# DWDM_-.net
KiCad netlist of a schematic drawn in Altium Designer
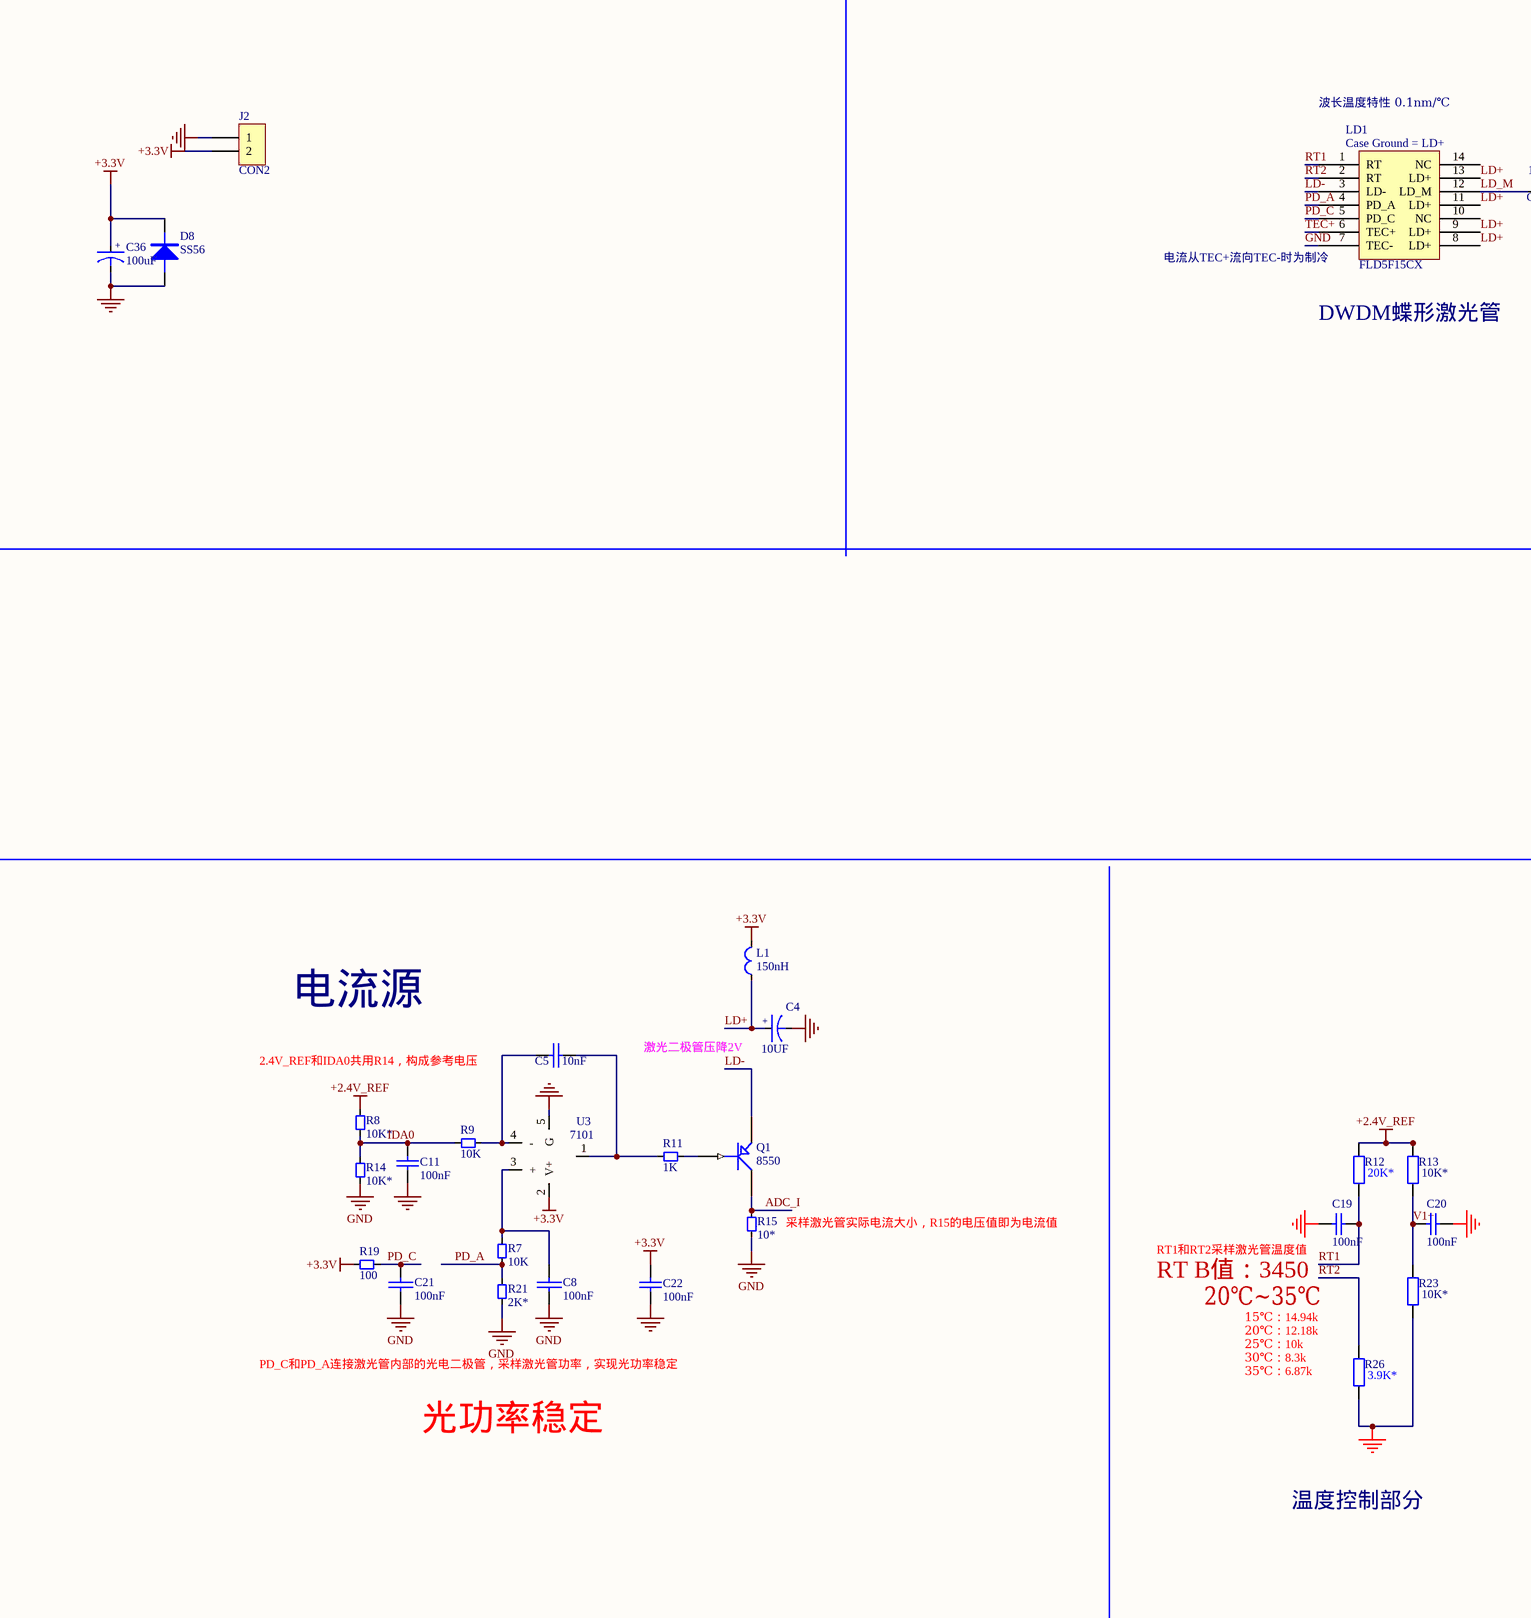
[diagram p0: DWDM蝶形激光管驱动器-线性.SchDoc, left]
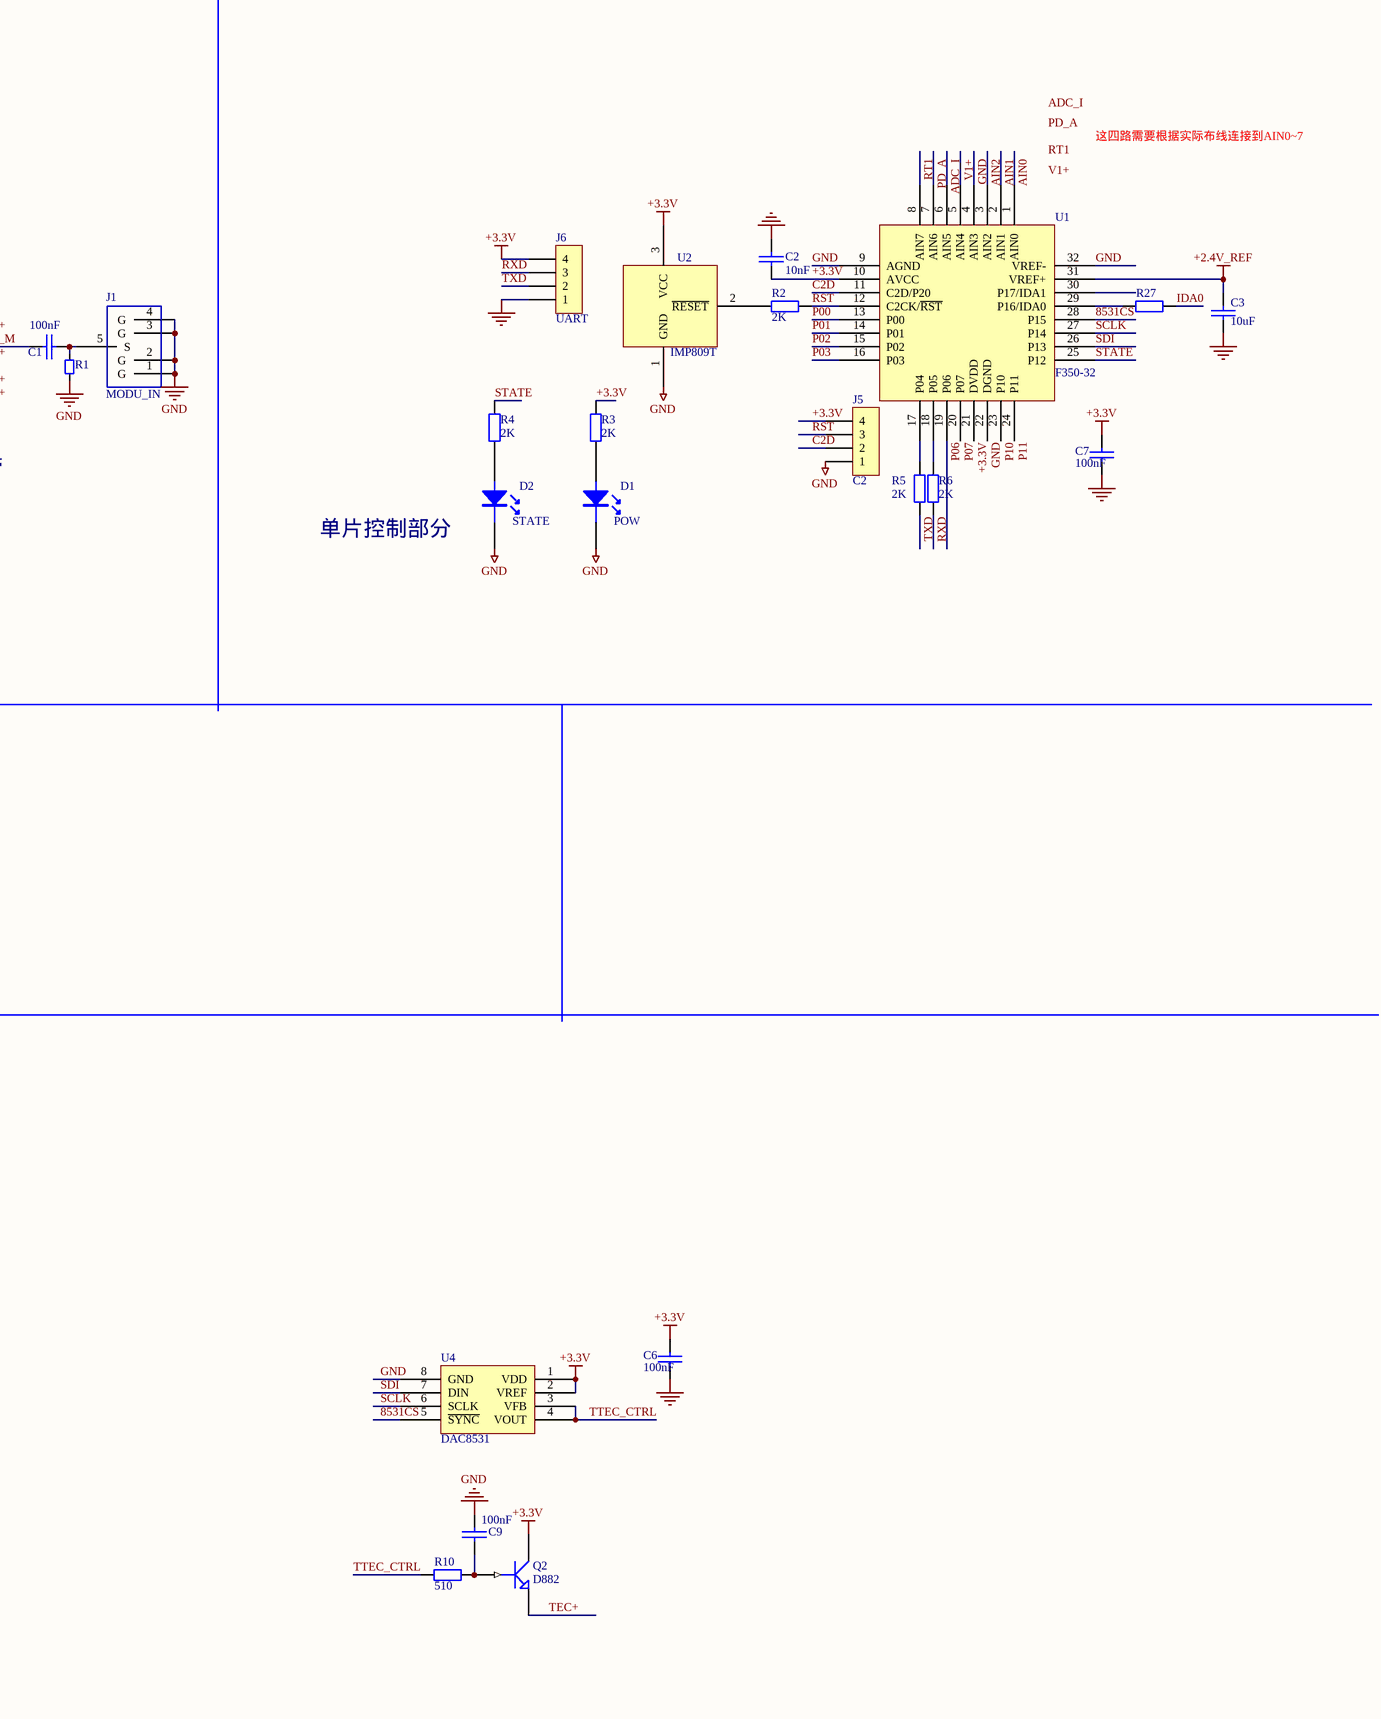
[diagram p1: DWDM蝶形激光管驱动器-线性.SchDoc, right]

(export (version "E")
  (design (tool "Eeschema 10.0.6"))
  (components
    (comp (ref "C1")
      (value "100nF")
      (footprint "0805")
      (description "Capacitor")
      (libsource (lib "*") (part "CAP"))
    )
    (comp (ref "C2")
      (value "10nF")
      (footprint "0805")
      (description "Capacitor")
      (libsource (lib "*") (part "CAP"))
    )
    (comp (ref "C3")
      (value "10uF")
      (footprint "0805")
      (description "Capacitor")
      (libsource (lib "*") (part "CAP"))
    )
    (comp (ref "C4") (value "10UF") (footprint "1206-C") (libsource (lib "高精时频SCHLIB") (part "CAP-POL-TA")))
    (comp (ref "C5")
      (value "10nF")
      (footprint "0805")
      (description "Capacitor")
      (libsource (lib "*") (part "CAP"))
    )
    (comp (ref "C6")
      (value "100nF")
      (footprint "0805")
      (description "Capacitor")
      (libsource (lib "*") (part "CAP"))
    )
    (comp (ref "C7")
      (value "100nF")
      (footprint "0805")
      (description "Capacitor")
      (libsource (lib "*") (part "CAP"))
    )
    (comp (ref "C8")
      (value "100nF")
      (footprint "0805")
      (description "Capacitor")
      (libsource (lib "*") (part "CAP"))
    )
    (comp (ref "C9")
      (value "100nF")
      (footprint "0805")
      (description "Capacitor")
      (libsource (lib "*") (part "CAP"))
    )
    (comp (ref "C11")
      (value "100nF")
      (footprint "0805")
      (description "Capacitor")
      (libsource (lib "*") (part "Cap"))
    )
    (comp (ref "C19")
      (value "100nF")
      (footprint "0805")
      (description "Capacitor")
      (libsource (lib "*") (part "Cap"))
    )
    (comp (ref "C20")
      (value "100nF")
      (footprint "0805")
      (description "Capacitor")
      (libsource (lib "*") (part "Cap"))
    )
    (comp (ref "C21")
      (value "100nF")
      (footprint "0805")
      (description "Capacitor")
      (libsource (lib "*") (part "CAP"))
    )
    (comp (ref "C22")
      (value "100nF")
      (footprint "0805")
      (description "Capacitor")
      (libsource (lib "*") (part "Cap"))
    )
    (comp (ref "C36") (value "100uF") (footprint "C6032") (libsource (lib "高精时频SCHLIB") (part "CAP-POL-TA")))
    (comp (ref "D1") (value "POW") (footprint "LED.3") (libsource (lib "*") (part "LED")))
    (comp (ref "D2") (value "STATE") (footprint "LED.3") (libsource (lib "*") (part "LED")))
    (comp (ref "D8") (value "SS56") (footprint "1808D-") (libsource (lib "高精时频SCHLIB") (part "DIODE")))
    (comp (ref "J1") (value "MODU_IN") (footprint "SMA") (libsource (lib "高精时频SCHLIB") (part "SMA")))
    (comp (ref "J2")
      (value "CON2")
      (footprint "JK2-394-F")
      (description "Connector")
      (libsource (lib "高精时频SCHLIB") (part "CON2"))
    )
    (comp (ref "J5")
      (value "C2")
      (footprint "SIP-4-Z")
      (description "Connector")
      (libsource (lib "*") (part "CON4"))
    )
    (comp (ref "J6")
      (value "UART")
      (footprint "SIP-4-Z")
      (description "Connector")
      (libsource (lib "*") (part "CON4"))
    )
    (comp (ref "L1") (value "150nH") (footprint "0805") (libsource (lib "高精时频SCHLIB") (part "INDUCTOR")))
    (comp (ref "LD1")
      (value "FLD5F15CX")
      (footprint "CM96/LC97-N")
      (libsource (lib "CFX") (part "FLD5F15CX"))
    )
    (comp (ref "Q1") (value "8550") (footprint "SOT-23") (libsource (lib "高精时频SCHLIB") (part "PNP-SOT23")))
    (comp (ref "Q2")
      (value "D882")
      (footprint "TO-252-D882")
      (libsource (lib "高精时频SCHLIB") (part "NPN-TO252"))
    )
    (comp (ref "R1") (value "~") (footprint "0805") (libsource (lib "高精时频SCHLIB") (part "RES")))
    (comp (ref "R2") (value "2K") (footprint "0805") (libsource (lib "") (part "RES2_1")))
    (comp (ref "R3") (value "2K") (footprint "0805") (libsource (lib "*") (part "RES2")))
    (comp (ref "R4") (value "2K") (footprint "0805") (libsource (lib "*") (part "RES2")))
    (comp (ref "R5") (value "2K") (footprint "0805") (libsource (lib "*") (part "RES2")))
    (comp (ref "R6") (value "2K") (footprint "0805") (libsource (lib "*") (part "RES2")))
    (comp (ref "R7") (value "10K") (footprint "0805") (libsource (lib "高精时频SCHLIB") (part "RES")))
    (comp (ref "R8") (value "10K*") (footprint "0805") (libsource (lib "高精时频SCHLIB") (part "RES")))
    (comp (ref "R9") (value "10K") (footprint "0805") (libsource (lib "高精时频SCHLIB") (part "RES")))
    (comp (ref "R10") (value "510") (footprint "0805") (libsource (lib "") (part "RES2_1")))
    (comp (ref "R11") (value "1K") (footprint "0805") (libsource (lib "高精时频SCHLIB") (part "RES")))
    (comp (ref "R12")
      (value "20K*")
      (footprint "0805")
      (description "Resistor")
      (libsource (lib "*") (part "Res2"))
    )
    (comp (ref "R13")
      (value "10K*")
      (footprint "0805")
      (description "Resistor")
      (libsource (lib "*") (part "Res2"))
    )
    (comp (ref "R14") (value "10K*") (footprint "0805") (libsource (lib "高精时频SCHLIB") (part "RES")))
    (comp (ref "R15") (value "10*") (footprint "0805") (libsource (lib "高精时频SCHLIB") (part "RES")))
    (comp (ref "R19") (value "100") (footprint "0805") (libsource (lib "高精时频SCHLIB") (part "RES")))
    (comp (ref "R21") (value "2K*") (footprint "0805") (libsource (lib "高精时频SCHLIB") (part "RES")))
    (comp (ref "R23")
      (value "10K*")
      (footprint "0805")
      (description "Resistor")
      (libsource (lib "*") (part "Res2"))
    )
    (comp (ref "R26")
      (value "3.9K*")
      (footprint "0805")
      (description "Resistor")
      (libsource (lib "*") (part "Res2"))
    )
    (comp (ref "R27") (value "~") (footprint "0805") (libsource (lib "") (part "RES2_1")))
    (comp (ref "U1") (value "F350-32") (footprint "LQFP32") (libsource (lib "*") (part "C8051F350-32")))
    (comp (ref "U2") (value "IMP809T") (footprint "SOT-23-P") (libsource (lib "*") (part "IMP809")))
    (comp (ref "U3") (value "7101") (footprint "PDSO-G5-DBV") (libsource (lib "*") (part "LMC7101")))
    (comp (ref "U4") (value "DAC8531") (footprint "PDSO-G8-DGK") (libsource (lib "*") (part "DAC8531")))
  )
  (nets
    (net (code "1") (name "+2.4V_REF") (class "Default")
      (node (ref "C3") (pin "1") (pinfunction "1_1") (pintype "passive"))
      (node (ref "R12") (pin "2") (pinfunction "2_2") (pintype "passive"))
      (node (ref "R13") (pin "2") (pinfunction "2_2") (pintype "passive"))
      (node (ref "R8") (pin "2") (pinfunction "2_2") (pintype "passive"))
      (node (ref "U1") (pin "31") (pinfunction "VREF+_31") (pintype "passive"))
    )
    (net (code "2") (name "+3.3V") (class "Default")
      (node (ref "C2") (pin "1") (pinfunction "1_1") (pintype "passive"))
      (node (ref "C22") (pin "2") (pinfunction "2_2") (pintype "passive"))
      (node (ref "C36") (pin "1") (pinfunction "1_1") (pintype "passive"))
      (node (ref "C6") (pin "1") (pinfunction "1_1") (pintype "passive"))
      (node (ref "C7") (pin "1") (pinfunction "1_1") (pintype "passive"))
      (node (ref "D8") (pin "2") (pinfunction "Cathode_2") (pintype "passive"))
      (node (ref "J2") (pin "2") (pinfunction "2_2") (pintype "passive"))
      (node (ref "J5") (pin "4") (pinfunction "4_4") (pintype "passive"))
      (node (ref "J6") (pin "4") (pinfunction "4_4") (pintype "passive"))
      (node (ref "L1") (pin "2") (pinfunction "2_2") (pintype "passive"))
      (node (ref "Q2") (pin "2") (pinfunction "C_2") (pintype "passive"))
      (node (ref "R19") (pin "1") (pinfunction "1_1") (pintype "passive"))
      (node (ref "R3") (pin "2") (pinfunction "2_2") (pintype "passive"))
      (node (ref "U1") (pin "10") (pinfunction "AVCC_10") (pintype "passive"))
      (node (ref "U1") (pin "21") (pinfunction "DVDD_21") (pintype "passive"))
      (node (ref "U2") (pin "3") (pinfunction "VCC_3") (pintype "passive"))
      (node (ref "U3") (pin "2") (pinfunction "V+_2") (pintype "passive"))
      (node (ref "U4") (pin "1") (pinfunction "VDD_1") (pintype "passive"))
      (node (ref "U4") (pin "2") (pinfunction "VREF_2") (pintype "passive"))
    )
    (net (code "3") (name "/8531CS") (class "Default")
      (node (ref "U1") (pin "28") (pinfunction "P15_28") (pintype "passive"))
      (node (ref "U4") (pin "5") (pinfunction "~{SYNC}_5") (pintype "passive"))
    )
    (net (code "5") (name "/ADC_I") (class "Default")
      (node (ref "Q1") (pin "3") (pinfunction "C_3") (pintype "passive"))
      (node (ref "R15") (pin "2") (pinfunction "2_2") (pintype "passive"))
      (node (ref "U1") (pin "6") (pinfunction "AIN5_6") (pintype "passive"))
    )
    (net (code "6") (name "/AIN0") (class "Default")
      (node (ref "U1") (pin "1") (pinfunction "AIN0_1") (pintype "passive"))
    )
    (net (code "7") (name "/AIN1") (class "Default")
      (node (ref "U1") (pin "2") (pinfunction "AIN1_2") (pintype "passive"))
    )
    (net (code "8") (name "/AIN2") (class "Default")
      (node (ref "U1") (pin "3") (pinfunction "AIN2_3") (pintype "passive"))
    )
    (net (code "9") (name "/C2D") (class "Default")
      (node (ref "J5") (pin "2") (pinfunction "2_2") (pintype "passive"))
      (node (ref "U1") (pin "11") (pinfunction "C2D/P20_11") (pintype "passive"))
    )
    (net (code "10") (name "/IDA0") (class "Default")
      (node (ref "C11") (pin "2") (pinfunction "2_2") (pintype "passive"))
      (node (ref "R14") (pin "2") (pinfunction "2_2") (pintype "passive"))
      (node (ref "R27") (pin "1") (pinfunction "1_1") (pintype "passive"))
      (node (ref "R8") (pin "1") (pinfunction "1_1") (pintype "passive"))
      (node (ref "R9") (pin "2") (pinfunction "2_2") (pintype "passive"))
    )
    (net (code "11") (name "/LD+") (class "Default")
      (node (ref "C4") (pin "1") (pinfunction "1_1") (pintype "passive"))
      (node (ref "L1") (pin "1") (pinfunction "1_1") (pintype "passive"))
      (node (ref "LD1") (pin "11") (pinfunction "LD+_11") (pintype "passive"))
      (node (ref "LD1") (pin "13") (pinfunction "LD+_13") (pintype "passive"))
      (node (ref "LD1") (pin "8") (pinfunction "LD+_8") (pintype "passive"))
      (node (ref "LD1") (pin "9") (pinfunction "LD+_9") (pintype "passive"))
    )
    (net (code "12") (name "/LD-") (class "Default")
      (node (ref "LD1") (pin "3") (pinfunction "LD-_3") (pintype "passive"))
      (node (ref "Q1") (pin "2") (pinfunction "E_2") (pintype "passive"))
    )
    (net (code "13") (name "/LD_M") (class "Default")
      (node (ref "C1") (pin "1") (pinfunction "1_1") (pintype "passive"))
      (node (ref "LD1") (pin "12") (pinfunction "LD_M_12") (pintype "passive"))
    )
    (net (code "14") (name "/P00") (class "Default")
      (node (ref "U1") (pin "13") (pinfunction "P00_13") (pintype "passive"))
    )
    (net (code "15") (name "/P01") (class "Default")
      (node (ref "U1") (pin "14") (pinfunction "P01_14") (pintype "passive"))
    )
    (net (code "16") (name "/P02") (class "Default")
      (node (ref "U1") (pin "15") (pinfunction "P02_15") (pintype "passive"))
    )
    (net (code "17") (name "/P03") (class "Default")
      (node (ref "U1") (pin "16") (pinfunction "P03_16") (pintype "passive"))
    )
    (net (code "18") (name "/P06") (class "Default")
      (node (ref "U1") (pin "19") (pinfunction "P06_19") (pintype "passive"))
    )
    (net (code "19") (name "/P07") (class "Default")
      (node (ref "U1") (pin "20") (pinfunction "P07_20") (pintype "passive"))
    )
    (net (code "20") (name "/P10") (class "Default")
      (node (ref "U1") (pin "23") (pinfunction "P10_23") (pintype "passive"))
    )
    (net (code "21") (name "/P11") (class "Default")
      (node (ref "U1") (pin "24") (pinfunction "P11_24") (pintype "passive"))
    )
    (net (code "22") (name "/PD_A") (class "Default")
      (node (ref "LD1") (pin "4") (pinfunction "PD_A_4") (pintype "passive"))
      (node (ref "R21") (pin "2") (pinfunction "2_2") (pintype "passive"))
      (node (ref "R7") (pin "2") (pinfunction "2_2") (pintype "passive"))
      (node (ref "U1") (pin "7") (pinfunction "AIN6_7") (pintype "passive"))
    )
    (net (code "23") (name "/PD_C") (class "Default")
      (node (ref "C21") (pin "2") (pinfunction "2_2") (pintype "passive"))
      (node (ref "LD1") (pin "5") (pinfunction "PD_C_5") (pintype "passive"))
      (node (ref "R19") (pin "2") (pinfunction "2_2") (pintype "passive"))
    )
    (net (code "24") (name "/RST") (class "Default")
      (node (ref "J5") (pin "3") (pinfunction "3_3") (pintype "passive"))
      (node (ref "R2") (pin "1") (pinfunction "1_1") (pintype "passive"))
      (node (ref "U1") (pin "12") (pinfunction "C2CK/~{RST}_12") (pintype "passive"))
    )
    (net (code "25") (name "/RT1") (class "Default")
      (node (ref "C19") (pin "1") (pinfunction "1_1") (pintype "passive"))
      (node (ref "LD1") (pin "1") (pinfunction "RT_1") (pintype "passive"))
      (node (ref "R12") (pin "1") (pinfunction "1_1") (pintype "passive"))
      (node (ref "U1") (pin "8") (pinfunction "AIN7_8") (pintype "passive"))
    )
    (net (code "26") (name "/RT2") (class "Default")
      (node (ref "LD1") (pin "2") (pinfunction "RT_2") (pintype "passive"))
      (node (ref "R26") (pin "2") (pinfunction "2_2") (pintype "passive"))
    )
    (net (code "27") (name "/RXD") (class "Default")
      (node (ref "J6") (pin "3") (pinfunction "3_3") (pintype "passive"))
      (node (ref "R6") (pin "1") (pinfunction "1_1") (pintype "passive"))
    )
    (net (code "28") (name "/SCLK") (class "Default")
      (node (ref "U1") (pin "27") (pinfunction "P14_27") (pintype "passive"))
      (node (ref "U4") (pin "6") (pinfunction "SCLK_6") (pintype "passive"))
    )
    (net (code "29") (name "/SDI") (class "Default")
      (node (ref "U1") (pin "26") (pinfunction "P13_26") (pintype "passive"))
      (node (ref "U4") (pin "7") (pinfunction "DIN_7") (pintype "passive"))
    )
    (net (code "30") (name "/STATE") (class "Default")
      (node (ref "R4") (pin "2") (pinfunction "2_2") (pintype "passive"))
      (node (ref "U1") (pin "25") (pinfunction "P12_25") (pintype "passive"))
    )
    (net (code "31") (name "/TEC+") (class "Default")
      (node (ref "LD1") (pin "6") (pinfunction "TEC+_6") (pintype "passive"))
      (node (ref "Q2") (pin "1") (pinfunction "E_1") (pintype "passive"))
    )
    (net (code "32") (name "/TTEC_CTRL") (class "Default")
      (node (ref "R10") (pin "2") (pinfunction "2_2") (pintype "passive"))
      (node (ref "U4") (pin "3") (pinfunction "VFB_3") (pintype "passive"))
      (node (ref "U4") (pin "4") (pinfunction "VOUT_4") (pintype "passive"))
    )
    (net (code "33") (name "/TXD") (class "Default")
      (node (ref "J6") (pin "2") (pinfunction "2_2") (pintype "passive"))
      (node (ref "R5") (pin "1") (pinfunction "1_1") (pintype "passive"))
    )
    (net (code "34") (name "/V1+") (class "Default")
      (node (ref "C20") (pin "1") (pinfunction "1_1") (pintype "passive"))
      (node (ref "R13") (pin "1") (pinfunction "1_1") (pintype "passive"))
      (node (ref "R23") (pin "2") (pinfunction "2_2") (pintype "passive"))
      (node (ref "U1") (pin "5") (pinfunction "AIN4_5") (pintype "passive"))
    )
    (net (code "35") (name "GND") (class "Default")
      (node (ref "C11") (pin "1") (pinfunction "1_1") (pintype "passive"))
      (node (ref "C19") (pin "2") (pinfunction "2_2") (pintype "passive"))
      (node (ref "C2") (pin "2") (pinfunction "2_2") (pintype "passive"))
      (node (ref "C20") (pin "2") (pinfunction "2_2") (pintype "passive"))
      (node (ref "C21") (pin "1") (pinfunction "1_1") (pintype "passive"))
      (node (ref "C22") (pin "1") (pinfunction "1_1") (pintype "passive"))
      (node (ref "C3") (pin "2") (pinfunction "2_2") (pintype "passive"))
      (node (ref "C36") (pin "2") (pinfunction "2_2") (pintype "passive"))
      (node (ref "C4") (pin "2") (pinfunction "2_2") (pintype "passive"))
      (node (ref "C6") (pin "2") (pinfunction "2_2") (pintype "passive"))
      (node (ref "C7") (pin "2") (pinfunction "2_2") (pintype "passive"))
      (node (ref "C8") (pin "1") (pinfunction "1_1") (pintype "passive"))
      (node (ref "C9") (pin "2") (pinfunction "2_2") (pintype "passive"))
      (node (ref "D1") (pin "2") (pinfunction "K_2") (pintype "passive"))
      (node (ref "D2") (pin "2") (pinfunction "K_2") (pintype "passive"))
      (node (ref "D8") (pin "1") (pinfunction "Anode_1") (pintype "passive"))
      (node (ref "J1") (pin "1") (pinfunction "G_1") (pintype "passive"))
      (node (ref "J1") (pin "2") (pinfunction "G_2") (pintype "passive"))
      (node (ref "J1") (pin "3") (pinfunction "G_3") (pintype "passive"))
      (node (ref "J1") (pin "4") (pinfunction "G_4") (pintype "passive"))
      (node (ref "J2") (pin "1") (pinfunction "1_1") (pintype "passive"))
      (node (ref "J5") (pin "1") (pinfunction "1_1") (pintype "passive"))
      (node (ref "J6") (pin "1") (pinfunction "1_1") (pintype "passive"))
      (node (ref "LD1") (pin "7") (pinfunction "TEC-_7") (pintype "passive"))
      (node (ref "R1") (pin "1") (pinfunction "1_1") (pintype "passive"))
      (node (ref "R14") (pin "1") (pinfunction "1_1") (pintype "passive"))
      (node (ref "R15") (pin "1") (pinfunction "1_1") (pintype "passive"))
      (node (ref "R21") (pin "1") (pinfunction "1_1") (pintype "passive"))
      (node (ref "R23") (pin "1") (pinfunction "1_1") (pintype "passive"))
      (node (ref "R26") (pin "1") (pinfunction "1_1") (pintype "passive"))
      (node (ref "U1") (pin "22") (pinfunction "DGND_22") (pintype "passive"))
      (node (ref "U1") (pin "32") (pinfunction "VREF-_32") (pintype "passive"))
      (node (ref "U1") (pin "4") (pinfunction "AIN3_4") (pintype "passive"))
      (node (ref "U1") (pin "9") (pinfunction "AGND_9") (pintype "passive"))
      (node (ref "U2") (pin "1") (pinfunction "GND_1") (pintype "passive"))
      (node (ref "U3") (pin "5") (pinfunction "G_5") (pintype "passive"))
      (node (ref "U4") (pin "8") (pinfunction "GND_8") (pintype "passive"))
    )
    (net (code "36") (name "Net-(C5-Pad2)") (class "Default")
      (node (ref "C5") (pin "2") (pinfunction "2_2") (pintype "passive"))
      (node (ref "R11") (pin "1") (pinfunction "1_1") (pintype "passive"))
      (node (ref "U3") (pin "1") (pintype "passive"))
    )
    (net (code "37") (name "Net-(D1-A)") (class "Default")
      (node (ref "D1") (pin "1") (pinfunction "A_1") (pintype "passive"))
      (node (ref "R3") (pin "1") (pinfunction "1_1") (pintype "passive"))
    )
    (net (code "38") (name "Net-(D2-A)") (class "Default")
      (node (ref "D2") (pin "1") (pinfunction "A_1") (pintype "passive"))
      (node (ref "R4") (pin "1") (pinfunction "1_1") (pintype "passive"))
    )
    (net (code "39") (name "Net-(J1-S)") (class "Default")
      (node (ref "C1") (pin "2") (pinfunction "2_2") (pintype "passive"))
      (node (ref "J1") (pin "5") (pinfunction "S_5") (pintype "passive"))
      (node (ref "R1") (pin "2") (pinfunction "2_2") (pintype "passive"))
    )
    (net (code "40") (name "Net-(Q1-B)") (class "Default")
      (node (ref "Q1") (pin "1") (pinfunction "B_1") (pintype "input"))
      (node (ref "R11") (pin "2") (pinfunction "2_2") (pintype "passive"))
    )
    (net (code "41") (name "Net-(Q2-B)") (class "Default")
      (node (ref "C9") (pin "1") (pinfunction "1_1") (pintype "passive"))
      (node (ref "Q2") (pin "3") (pinfunction "B_3") (pintype "input"))
      (node (ref "R10") (pin "1") (pinfunction "1_1") (pintype "passive"))
    )
    (net (code "42") (name "Net-(U1-P04)") (class "Default")
      (node (ref "R5") (pin "2") (pinfunction "2_2") (pintype "passive"))
      (node (ref "U1") (pin "17") (pinfunction "P04_17") (pintype "passive"))
    )
    (net (code "43") (name "Net-(U1-P05)") (class "Default")
      (node (ref "R6") (pin "2") (pinfunction "2_2") (pintype "passive"))
      (node (ref "U1") (pin "18") (pinfunction "P05_18") (pintype "passive"))
    )
    (net (code "44") (name "Net-(U1-P16{slash}IDA0)") (class "Default")
      (node (ref "R27") (pin "2") (pinfunction "2_2") (pintype "passive"))
      (node (ref "U1") (pin "29") (pinfunction "P16/IDA0_29") (pintype "passive"))
    )
    (net (code "45") (name "Net-(U2-~{RESET})") (class "Default")
      (node (ref "R2") (pin "2") (pinfunction "2_2") (pintype "passive"))
      (node (ref "U2") (pin "2") (pinfunction "~{RESET}_2") (pintype "passive"))
    )
    (net (code "46") (name "Net-(U3-+)") (class "Default")
      (node (ref "C8") (pin "2") (pinfunction "2_2") (pintype "passive"))
      (node (ref "R7") (pin "1") (pinfunction "1_1") (pintype "passive"))
      (node (ref "U3") (pin "3") (pinfunction "+_3") (pintype "passive"))
    )
    (net (code "47") (name "Net-(U3--)") (class "Default")
      (node (ref "C5") (pin "1") (pinfunction "1_1") (pintype "passive"))
      (node (ref "R9") (pin "1") (pinfunction "1_1") (pintype "passive"))
      (node (ref "U3") (pin "4") (pinfunction "-_4") (pintype "passive"))
    )
    (net (code "48") (name "unconnected-(LD1-NC-Pad10)") (class "Default")
      (node (ref "LD1") (pin "10") (pinfunction "NC_10") (pintype "passive"))
    )
    (net (code "49") (name "unconnected-(LD1-NC-Pad14)") (class "Default")
      (node (ref "LD1") (pin "14") (pinfunction "NC_14") (pintype "passive"))
    )
    (net (code "50") (name "unconnected-(U1-P17{slash}IDA1-Pad30)") (class "Default")
      (node (ref "U1") (pin "30") (pinfunction "P17/IDA1_30") (pintype "passive"))
    )
  )
)
